# s-ispv2.net
KiCad netlist of a schematic drawn in EAGLE
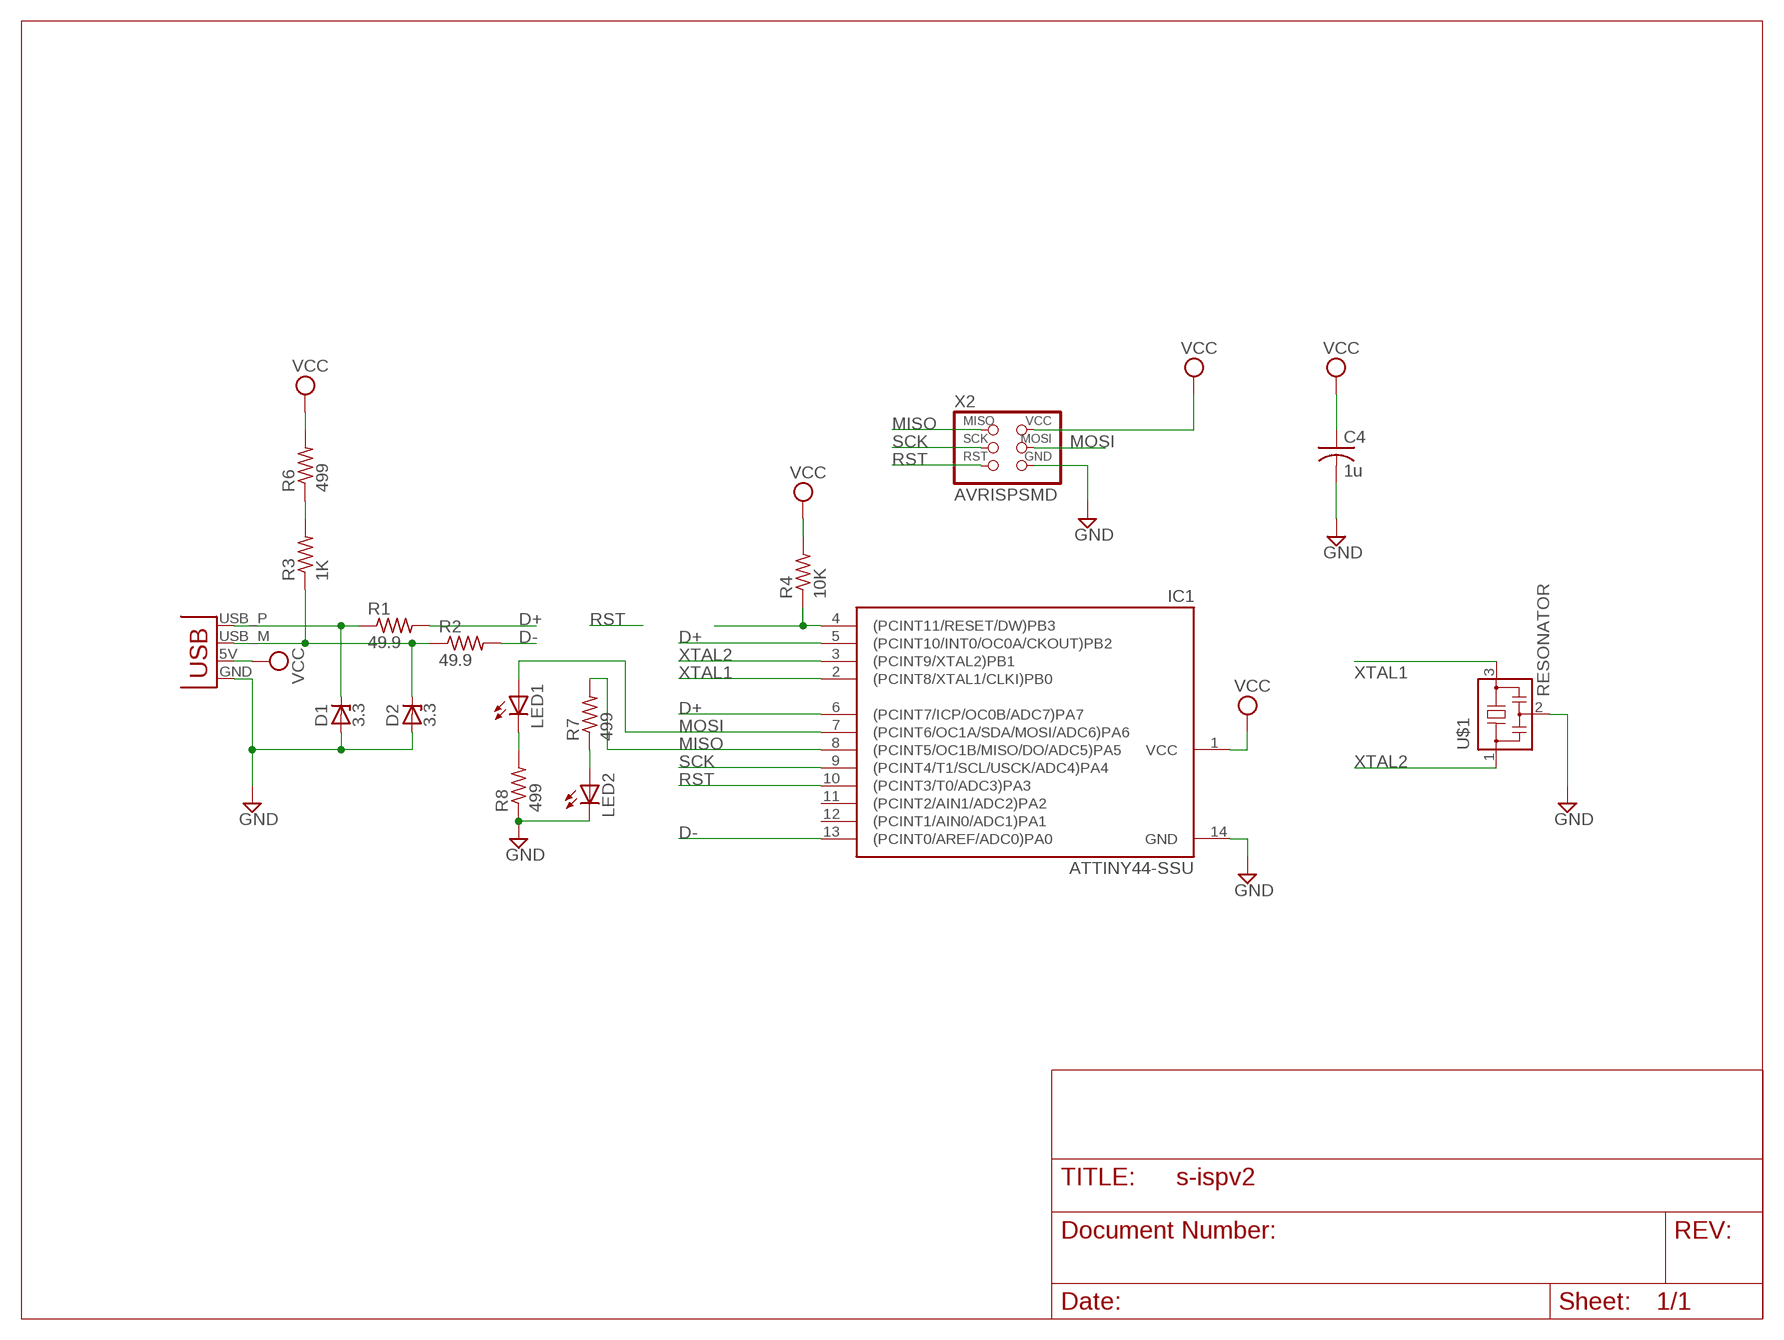
[diagram p0: schematic, sheet 1]

(export (version "E")
  (design (tool "Eeschema 10.0.6"))
  (components
    (comp (ref "C4")
      (value "1u")
      (footprint "eagle-import:C1206")
      (libsource (lib "eagle-import") (part "C-USC1206"))
    )
    (comp (ref "D1")
      (value "3.3")
      (footprint "eagle-import:SOD123")
      (libsource (lib "eagle-import") (part "ZENER_DIODESOD123"))
    )
    (comp (ref "D2")
      (value "3.3")
      (footprint "eagle-import:SOD123")
      (libsource (lib "eagle-import") (part "ZENER_DIODESOD123"))
    )
    (comp (ref "IC1")
      (value "ATTINY44-SSU")
      (footprint "eagle-import:SOIC14")
      (libsource (lib "eagle-import") (part "ATTINY44-SSU"))
    )
    (comp (ref "LED1")
      (value "LEDSMT1206")
      (footprint "eagle-import:1206")
      (libsource (lib "eagle-import") (part "LEDSMT1206"))
    )
    (comp (ref "LED2")
      (value "LEDSMT1206")
      (footprint "eagle-import:1206")
      (libsource (lib "eagle-import") (part "LEDSMT1206"))
    )
    (comp (ref "R1")
      (value "49.9")
      (footprint "eagle-import:R1206")
      (libsource (lib "eagle-import") (part "R-US_R1206"))
    )
    (comp (ref "R2")
      (value "49.9")
      (footprint "eagle-import:R1206")
      (libsource (lib "eagle-import") (part "R-US_R1206"))
    )
    (comp (ref "R3")
      (value "1K")
      (footprint "eagle-import:R1206")
      (libsource (lib "eagle-import") (part "R-US_R1206"))
    )
    (comp (ref "R4")
      (value "10K")
      (footprint "eagle-import:R1206")
      (libsource (lib "eagle-import") (part "R-US_R1206"))
    )
    (comp (ref "R6")
      (value "499")
      (footprint "eagle-import:R1206")
      (libsource (lib "eagle-import") (part "R-US_R1206"))
    )
    (comp (ref "R7")
      (value "499")
      (footprint "eagle-import:R1206")
      (libsource (lib "eagle-import") (part "R-US_R1206"))
    )
    (comp (ref "R8")
      (value "499")
      (footprint "eagle-import:R1206")
      (libsource (lib "eagle-import") (part "R-US_R1206"))
    )
    (comp (ref "U$1")
      (value "RESONATOR")
      (footprint "eagle-import:EFOBM")
      (libsource (lib "eagle-import") (part "RESONATOR"))
    )
    (comp (ref "X1")
      (value "USBPCB")
      (footprint "eagle-import:USB-A-PCB")
      (libsource (lib "eagle-import") (part "USBPCB"))
    )
    (comp (ref "X2")
      (value "AVRISPSMD")
      (footprint "eagle-import:2X03SMD")
      (libsource (lib "eagle-import") (part "AVRISPSMD"))
    )
  )
  (nets
    (net (code "1") (name "/D+") (class "Default")
      (node (ref "IC1") (pin "5") (pinfunction "(PCINT10/INT0/OC0A/CKOUT)PB2_5") (pintype "bidirectional"))
      (node (ref "IC1") (pin "6") (pinfunction "(PCINT7/ICP/OC0B/ADC7)PA7_6") (pintype "bidirectional"))
      (node (ref "R1") (pin "2") (pinfunction "2_2") (pintype "passive"))
    )
    (net (code "2") (name "/D-") (class "Default")
      (node (ref "IC1") (pin "13") (pinfunction "(PCINT0/AREF/ADC0)PA0_13") (pintype "bidirectional"))
      (node (ref "R2") (pin "2") (pinfunction "2_2") (pintype "passive"))
    )
    (net (code "3") (name "/MISO") (class "Default")
      (node (ref "IC1") (pin "8") (pinfunction "(PCINT5/OC1B/MISO/DO/ADC5)PA5_8") (pintype "bidirectional"))
      (node (ref "R7") (pin "2") (pinfunction "2_2") (pintype "passive"))
      (node (ref "X2") (pin "1") (pinfunction "MISO_1") (pintype "passive"))
    )
    (net (code "4") (name "/MOSI") (class "Default")
      (node (ref "IC1") (pin "7") (pinfunction "(PCINT6/OC1A/SDA/MOSI/ADC6)PA6_7") (pintype "bidirectional"))
      (node (ref "LED1") (pin "A") (pinfunction "A_A") (pintype "passive"))
      (node (ref "X2") (pin "4") (pinfunction "MOSI_4") (pintype "passive"))
    )
    (net (code "5") (name "/RST") (class "Default")
      (node (ref "IC1") (pin "10") (pinfunction "(PCINT3/T0/ADC3)PA3_10") (pintype "bidirectional"))
      (node (ref "IC1") (pin "4") (pinfunction "(PCINT11/RESET/DW)PB3_4") (pintype "bidirectional"))
      (node (ref "R4") (pin "1") (pinfunction "1_1") (pintype "passive"))
      (node (ref "X2") (pin "5") (pinfunction "RST_5") (pintype "passive"))
    )
    (net (code "6") (name "/SCK") (class "Default")
      (node (ref "IC1") (pin "9") (pinfunction "(PCINT4/T1/SCL/USCK/ADC4)PA4_9") (pintype "bidirectional"))
      (node (ref "X2") (pin "3") (pinfunction "SCK_3") (pintype "passive"))
    )
    (net (code "7") (name "/XTAL1") (class "Default")
      (node (ref "IC1") (pin "2") (pinfunction "(PCINT8/XTAL1/CLKI)PB0_2") (pintype "bidirectional"))
      (node (ref "U$1") (pin "3") (pinfunction "3_3") (pintype "passive"))
    )
    (net (code "8") (name "/XTAL2") (class "Default")
      (node (ref "IC1") (pin "3") (pinfunction "(PCINT9/XTAL2)PB1_3") (pintype "bidirectional"))
      (node (ref "U$1") (pin "1") (pinfunction "1_1") (pintype "passive"))
    )
    (net (code "9") (name "GND") (class "Default")
      (node (ref "C4") (pin "2") (pinfunction "2_2") (pintype "passive"))
      (node (ref "D1") (pin "ANODE") (pinfunction "ANODE_ANODE") (pintype "passive"))
      (node (ref "D2") (pin "ANODE") (pinfunction "ANODE_ANODE") (pintype "passive"))
      (node (ref "IC1") (pin "14") (pinfunction "GND_14") (pintype "power_in"))
      (node (ref "LED2") (pin "C") (pinfunction "C_C") (pintype "passive"))
      (node (ref "R8") (pin "1") (pinfunction "1_1") (pintype "passive"))
      (node (ref "U$1") (pin "2") (pinfunction "2_2") (pintype "passive"))
      (node (ref "X1") (pin "GND") (pinfunction "GND_GND") (pintype "bidirectional"))
      (node (ref "X2") (pin "6") (pinfunction "GND_6") (pintype "passive"))
    )
    (net (code "10") (name "Net-(LED1-PadC)") (class "Default")
      (node (ref "LED1") (pin "C") (pinfunction "C_C") (pintype "passive"))
      (node (ref "R8") (pin "2") (pinfunction "2_2") (pintype "passive"))
    )
    (net (code "11") (name "Net-(LED2-PadA)") (class "Default")
      (node (ref "LED2") (pin "A") (pinfunction "A_A") (pintype "passive"))
      (node (ref "R7") (pin "1") (pinfunction "1_1") (pintype "passive"))
    )
    (net (code "12") (name "Net-(R3-Pad2)") (class "Default")
      (node (ref "R3") (pin "2") (pinfunction "2_2") (pintype "passive"))
      (node (ref "R6") (pin "1") (pinfunction "1_1") (pintype "passive"))
    )
    (net (code "13") (name "Net-(X1-D+)") (class "Default")
      (node (ref "D1") (pin "CATHODE") (pinfunction "CATHODE_CATHODE") (pintype "passive"))
      (node (ref "R1") (pin "1") (pinfunction "1_1") (pintype "passive"))
      (node (ref "X1") (pin "USB_P") (pinfunction "D+_USB_P") (pintype "bidirectional"))
    )
    (net (code "14") (name "Net-(X1-D-)") (class "Default")
      (node (ref "D2") (pin "CATHODE") (pinfunction "CATHODE_CATHODE") (pintype "passive"))
      (node (ref "R2") (pin "1") (pinfunction "1_1") (pintype "passive"))
      (node (ref "R3") (pin "1") (pinfunction "1_1") (pintype "passive"))
      (node (ref "X1") (pin "USB_M") (pinfunction "D-_USB_M") (pintype "bidirectional"))
    )
    (net (code "15") (name "VCC") (class "Default")
      (node (ref "C4") (pin "1") (pinfunction "1_1") (pintype "passive"))
      (node (ref "IC1") (pin "1") (pinfunction "VCC_1") (pintype "power_in"))
      (node (ref "R4") (pin "2") (pinfunction "2_2") (pintype "passive"))
      (node (ref "R6") (pin "2") (pinfunction "2_2") (pintype "passive"))
      (node (ref "X1") (pin "5V") (pinfunction "VBUS_5V") (pintype "bidirectional"))
      (node (ref "X2") (pin "2") (pinfunction "VCC_2") (pintype "passive"))
    )
    (net (code "16") (name "unconnected-(IC1-(PCINT1{slash}AIN0{slash}ADC1)PA1-Pad12)") (class "Default")
      (node (ref "IC1") (pin "12") (pinfunction "(PCINT1/AIN0/ADC1)PA1_12") (pintype "bidirectional"))
    )
    (net (code "17") (name "unconnected-(IC1-(PCINT2{slash}AIN1{slash}ADC2)PA2-Pad11)") (class "Default")
      (node (ref "IC1") (pin "11") (pinfunction "(PCINT2/AIN1/ADC2)PA2_11") (pintype "bidirectional"))
    )
  )
)
